# PSU_Board.net
KiCad netlist of a schematic drawn in EAGLE
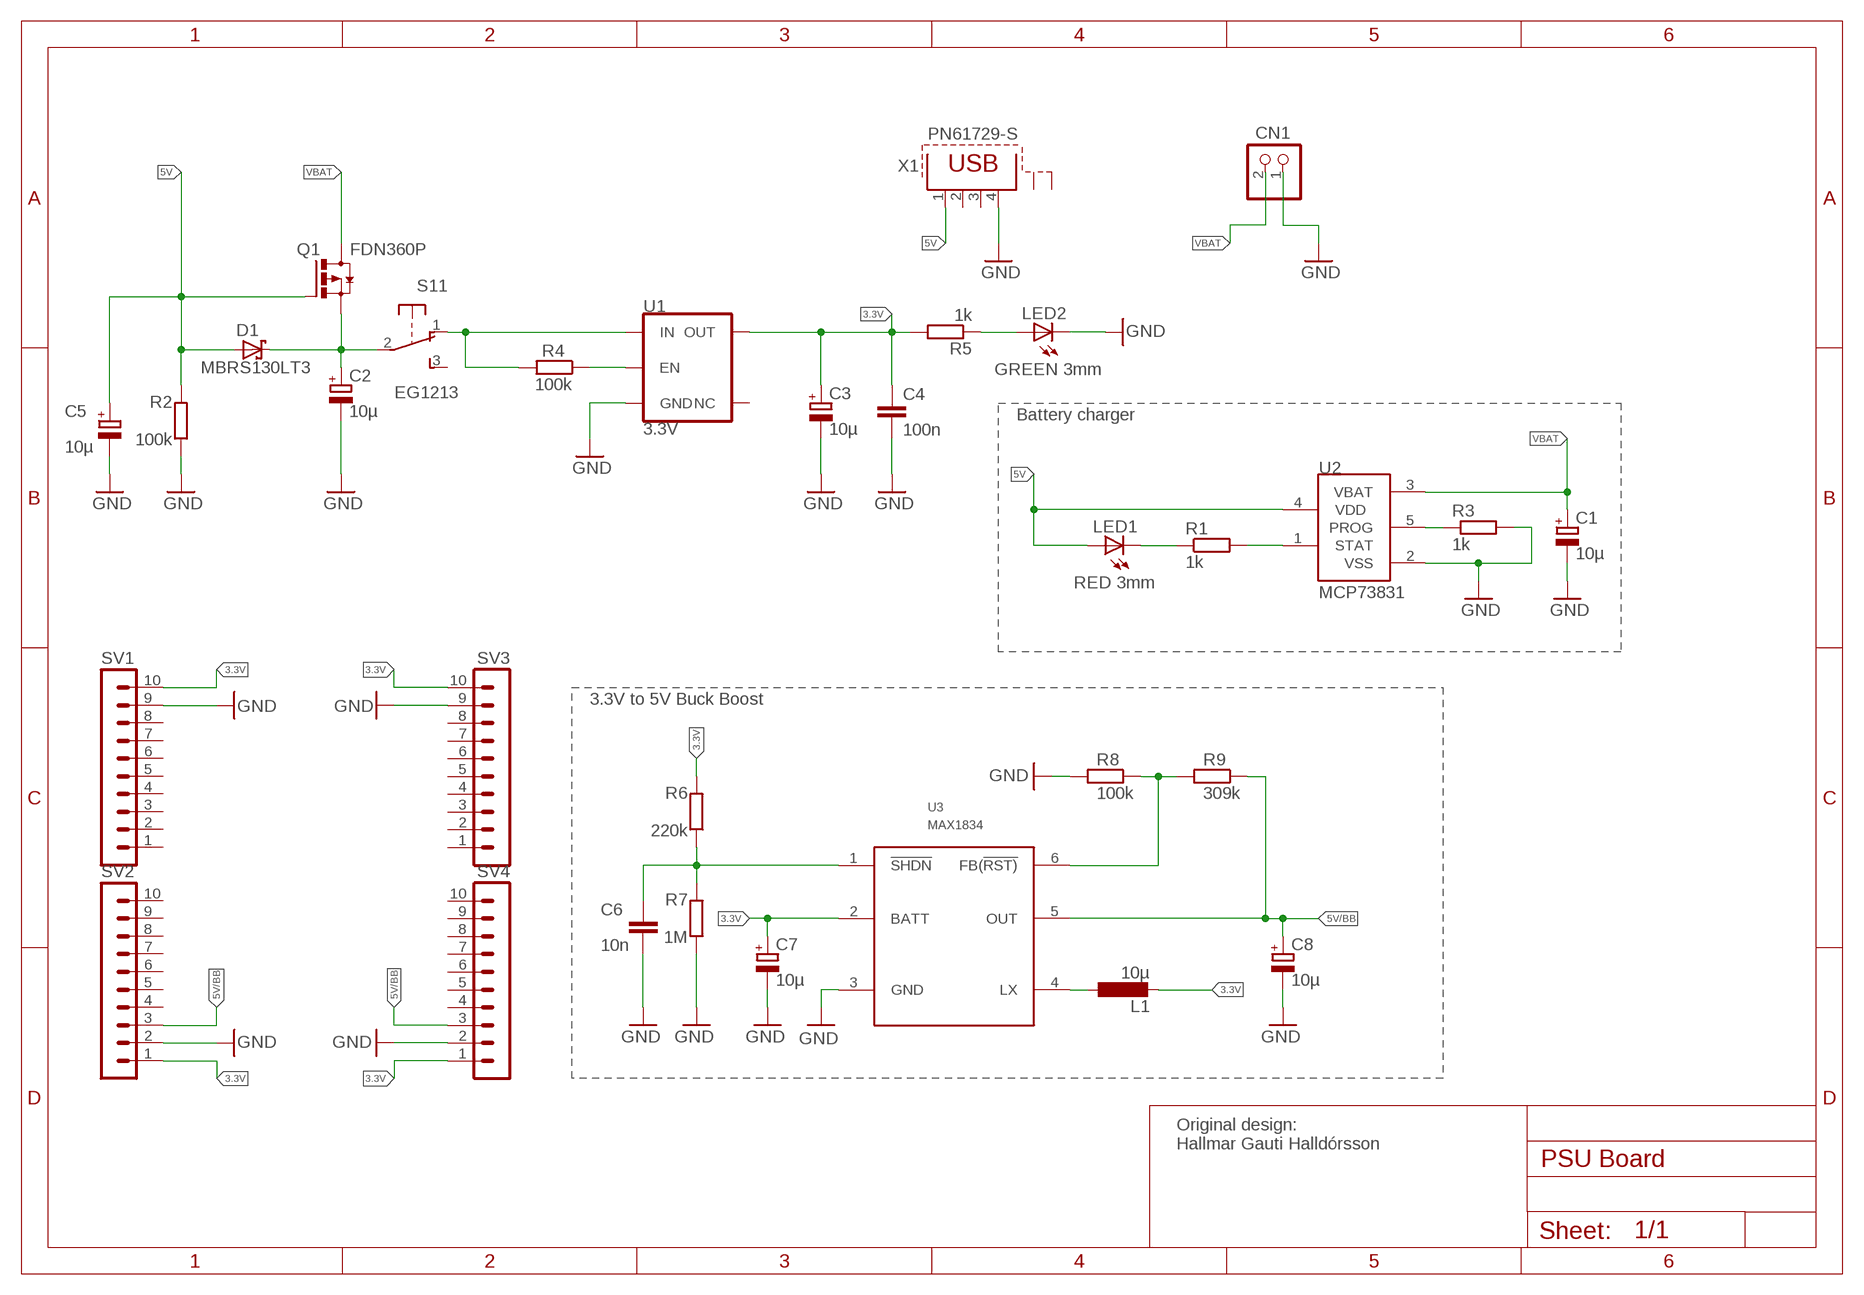
[diagram p0: schematic, sheet 1]

(export (version "E")
  (design (tool "Eeschema 10.0.6"))
  (components
    (comp (ref "C1")
      (value "10µ")
      (footprint "eagle-import:140CLH-0810")
      (libsource (lib "eagle-import") (part "CPOL-EU140CLH-0810"))
    )
    (comp (ref "C2")
      (value "10µ")
      (footprint "eagle-import:140CLH-0810")
      (libsource (lib "eagle-import") (part "CPOL-EU140CLH-0810"))
    )
    (comp (ref "C3")
      (value "10µ")
      (footprint "eagle-import:140CLH-0810")
      (libsource (lib "eagle-import") (part "CPOL-EU140CLH-0810"))
    )
    (comp (ref "C4")
      (value "100n")
      (footprint "eagle-import:C1206")
      (libsource (lib "eagle-import") (part "C-EUC1206"))
    )
    (comp (ref "C5")
      (value "10µ")
      (footprint "eagle-import:140CLH-0810")
      (libsource (lib "eagle-import") (part "CPOL-EU140CLH-0810"))
    )
    (comp (ref "C6")
      (value "10n")
      (footprint "eagle-import:C1206")
      (libsource (lib "eagle-import") (part "C-EUC1206"))
    )
    (comp (ref "C7")
      (value "10µ")
      (footprint "eagle-import:140CLH-0810")
      (libsource (lib "eagle-import") (part "CPOL-EU140CLH-0810"))
    )
    (comp (ref "C8")
      (value "10µ")
      (footprint "eagle-import:140CLH-0810")
      (libsource (lib "eagle-import") (part "CPOL-EU140CLH-0810"))
    )
    (comp (ref "CN1")
      (value "JST_2PIN-SMT")
      (footprint "eagle-import:JST-PH-2-SMT")
      (libsource (lib "eagle-import") (part "JST_2PIN-SMT"))
    )
    (comp (ref "D1")
      (value "MBRS130LT3")
      (footprint "eagle-import:SMB")
      (libsource (lib "eagle-import") (part "MBRS130LT3"))
    )
    (comp (ref "L1")
      (value "10µ")
      (footprint "eagle-import:L3216C")
      (libsource (lib "eagle-import") (part "L-EUL3216C"))
    )
    (comp (ref "LED1")
      (value "RED 3mm")
      (footprint "eagle-import:LED3MM")
      (libsource (lib "eagle-import") (part "LED3MM"))
    )
    (comp (ref "LED2")
      (value "GREEN 3mm")
      (footprint "eagle-import:LED3MM")
      (libsource (lib "eagle-import") (part "LED3MM"))
    )
    (comp (ref "Q1")
      (value "FDN360P")
      (footprint "eagle-import:SUPER-SOT3")
      (libsource (lib "eagle-import") (part "FDN360P"))
    )
    (comp (ref "R1")
      (value "1k")
      (footprint "eagle-import:M1206")
      (libsource (lib "eagle-import") (part "R-EU_M1206"))
    )
    (comp (ref "R2")
      (value "100k")
      (footprint "eagle-import:M1206")
      (libsource (lib "eagle-import") (part "R-EU_M1206"))
    )
    (comp (ref "R3")
      (value "1k")
      (footprint "eagle-import:M1206")
      (libsource (lib "eagle-import") (part "R-EU_M1206"))
    )
    (comp (ref "R4")
      (value "100k")
      (footprint "eagle-import:M1206")
      (libsource (lib "eagle-import") (part "R-EU_M1206"))
    )
    (comp (ref "R5")
      (value "1k")
      (footprint "eagle-import:M1206")
      (libsource (lib "eagle-import") (part "R-EU_M1206"))
    )
    (comp (ref "R6")
      (value "220k")
      (footprint "eagle-import:M1206")
      (libsource (lib "eagle-import") (part "R-EU_M1206"))
    )
    (comp (ref "R7")
      (value "1M")
      (footprint "eagle-import:M1206")
      (libsource (lib "eagle-import") (part "R-EU_M1206"))
    )
    (comp (ref "R8")
      (value "100k")
      (footprint "eagle-import:M1206")
      (libsource (lib "eagle-import") (part "R-EU_M1206"))
    )
    (comp (ref "R9")
      (value "309k")
      (footprint "eagle-import:M1206")
      (libsource (lib "eagle-import") (part "R-EU_M1206"))
    )
    (comp (ref "S1")
      (value "EG1213")
      (footprint "eagle-import:EG1213")
      (libsource (lib "eagle-import") (part "EG1213"))
    )
    (comp (ref "SV1")
      (value "MA10-1")
      (footprint "eagle-import:MA10-1")
      (libsource (lib "eagle-import") (part "MA10-1"))
    )
    (comp (ref "SV2")
      (value "MA10-1")
      (footprint "eagle-import:MA10-1")
      (libsource (lib "eagle-import") (part "MA10-1"))
    )
    (comp (ref "SV3")
      (value "MA10-1")
      (footprint "eagle-import:MA10-1")
      (libsource (lib "eagle-import") (part "MA10-1"))
    )
    (comp (ref "SV4")
      (value "MA10-1")
      (footprint "eagle-import:MA10-1")
      (libsource (lib "eagle-import") (part "MA10-1"))
    )
    (comp (ref "U1")
      (value "3.3V")
      (footprint "eagle-import:SOT23-5")
      (libsource (lib "eagle-import") (part "V_REG_AP2112K-3.3V"))
    )
    (comp (ref "U2")
      (value "MCP73831")
      (footprint "eagle-import:SOT23-5L")
      (libsource (lib "eagle-import") (part "MCP73831"))
    )
    (comp (ref "U3")
      (value "MAX1834")
      (footprint "eagle-import:SOT23-6")
      (libsource (lib "eagle-import") (part "MAX1834"))
    )
    (comp (ref "X1")
      (value "PN61729-S")
      (footprint "eagle-import:PN61729-S")
      (libsource (lib "eagle-import") (part "PN61729-S"))
    )
  )
  (nets
    (net (code "1") (name "3.3V") (class "Default")
      (node (ref "C3") (pin "+") (pinfunction "+_+") (pintype "passive"))
      (node (ref "C4") (pin "1") (pinfunction "1_1") (pintype "passive"))
      (node (ref "C7") (pin "+") (pinfunction "+_+") (pintype "passive"))
      (node (ref "L1") (pin "2") (pinfunction "2_2") (pintype "passive"))
      (node (ref "R5") (pin "2") (pinfunction "2_2") (pintype "passive"))
      (node (ref "R6") (pin "2") (pinfunction "2_2") (pintype "passive"))
      (node (ref "SV1") (pin "10") (pinfunction "10_10") (pintype "passive"))
      (node (ref "SV2") (pin "1") (pinfunction "1_1") (pintype "passive"))
      (node (ref "SV3") (pin "10") (pinfunction "10_10") (pintype "passive"))
      (node (ref "SV4") (pin "1") (pinfunction "1_1") (pintype "passive"))
      (node (ref "U1") (pin "5") (pinfunction "OUT_5") (pintype "passive"))
      (node (ref "U3") (pin "2") (pinfunction "BATT_2") (pintype "bidirectional"))
    )
    (net (code "2") (name "5V") (class "Default")
      (node (ref "C5") (pin "+") (pinfunction "+_+") (pintype "passive"))
      (node (ref "D1") (pin "A") (pinfunction "A_A") (pintype "passive"))
      (node (ref "LED1") (pin "A") (pinfunction "A_A") (pintype "passive"))
      (node (ref "Q1") (pin "1") (pinfunction "G_1") (pintype "passive"))
      (node (ref "R2") (pin "2") (pinfunction "2_2") (pintype "passive"))
      (node (ref "U2") (pin "4") (pinfunction "VDD_4") (pintype "bidirectional"))
      (node (ref "X1") (pin "1") (pinfunction "1_1") (pintype "passive"))
    )
    (net (code "3") (name "5V{slash}BB") (class "Default")
      (node (ref "C8") (pin "+") (pinfunction "+_+") (pintype "passive"))
      (node (ref "R9") (pin "1") (pinfunction "1_1") (pintype "passive"))
      (node (ref "SV2") (pin "3") (pinfunction "3_3") (pintype "passive"))
      (node (ref "SV4") (pin "3") (pinfunction "3_3") (pintype "passive"))
      (node (ref "U3") (pin "5") (pinfunction "OUT_5") (pintype "bidirectional"))
    )
    (net (code "4") (name "GND") (class "Default")
      (node (ref "C1") (pin "-") (pinfunction "-_-") (pintype "passive"))
      (node (ref "C2") (pin "-") (pinfunction "-_-") (pintype "passive"))
      (node (ref "C3") (pin "-") (pinfunction "-_-") (pintype "passive"))
      (node (ref "C4") (pin "2") (pinfunction "2_2") (pintype "passive"))
      (node (ref "C5") (pin "-") (pinfunction "-_-") (pintype "passive"))
      (node (ref "C6") (pin "2") (pinfunction "2_2") (pintype "passive"))
      (node (ref "C7") (pin "-") (pinfunction "-_-") (pintype "passive"))
      (node (ref "C8") (pin "-") (pinfunction "-_-") (pintype "passive"))
      (node (ref "CN1") (pin "1") (pinfunction "2_1") (pintype "passive"))
      (node (ref "LED2") (pin "K") (pinfunction "C_K") (pintype "passive"))
      (node (ref "R2") (pin "1") (pinfunction "1_1") (pintype "passive"))
      (node (ref "R3") (pin "2") (pinfunction "2_2") (pintype "passive"))
      (node (ref "R7") (pin "1") (pinfunction "1_1") (pintype "passive"))
      (node (ref "R8") (pin "2") (pinfunction "2_2") (pintype "passive"))
      (node (ref "SV1") (pin "9") (pinfunction "9_9") (pintype "passive"))
      (node (ref "SV2") (pin "2") (pinfunction "2_2") (pintype "passive"))
      (node (ref "SV3") (pin "9") (pinfunction "9_9") (pintype "passive"))
      (node (ref "SV4") (pin "2") (pinfunction "2_2") (pintype "passive"))
      (node (ref "U1") (pin "2") (pinfunction "GND_2") (pintype "input"))
      (node (ref "U2") (pin "2") (pinfunction "VSS_2") (pintype "bidirectional"))
      (node (ref "U3") (pin "3") (pinfunction "GND_3") (pintype "bidirectional"))
      (node (ref "X1") (pin "4") (pinfunction "4_4") (pintype "passive"))
    )
    (net (code "5") (name "Net-(LED1-C)") (class "Default")
      (node (ref "LED1") (pin "K") (pinfunction "C_K") (pintype "passive"))
      (node (ref "R1") (pin "1") (pinfunction "1_1") (pintype "passive"))
    )
    (net (code "6") (name "Net-(LED2-PadA)") (class "Default")
      (node (ref "LED2") (pin "A") (pinfunction "A_A") (pintype "passive"))
      (node (ref "R5") (pin "1") (pinfunction "1_1") (pintype "passive"))
    )
    (net (code "7") (name "Net-(Q1-S)") (class "Default")
      (node (ref "C2") (pin "+") (pinfunction "+_+") (pintype "passive"))
      (node (ref "D1") (pin "C") (pinfunction "C_C") (pintype "passive"))
      (node (ref "Q1") (pin "2") (pinfunction "S_2") (pintype "passive"))
      (node (ref "S1") (pin "2") (pinfunction "P_2") (pintype "passive"))
    )
    (net (code "8") (name "Net-(S1A-O)") (class "Default")
      (node (ref "R4") (pin "2") (pinfunction "2_2") (pintype "passive"))
      (node (ref "S1") (pin "1") (pinfunction "O_1") (pintype "passive"))
      (node (ref "U1") (pin "1") (pinfunction "IN_1") (pintype "input"))
    )
    (net (code "9") (name "Net-(U1-EN)") (class "Default")
      (node (ref "R4") (pin "1") (pinfunction "1_1") (pintype "passive"))
      (node (ref "U1") (pin "3") (pinfunction "EN_3") (pintype "input"))
    )
    (net (code "10") (name "Net-(U2-PROG)") (class "Default")
      (node (ref "R3") (pin "1") (pinfunction "1_1") (pintype "passive"))
      (node (ref "U2") (pin "5") (pinfunction "PROG_5") (pintype "bidirectional"))
    )
    (net (code "11") (name "Net-(U2-STAT)") (class "Default")
      (node (ref "R1") (pin "2") (pinfunction "2_2") (pintype "passive"))
      (node (ref "U2") (pin "1") (pinfunction "STAT_1") (pintype "bidirectional"))
    )
    (net (code "12") (name "Net-(U3-FB(~{RST}))") (class "Default")
      (node (ref "R8") (pin "1") (pinfunction "1_1") (pintype "passive"))
      (node (ref "R9") (pin "2") (pinfunction "2_2") (pintype "passive"))
      (node (ref "U3") (pin "6") (pinfunction "FB(~{RST})_6") (pintype "bidirectional"))
    )
    (net (code "13") (name "Net-(U3-LX)") (class "Default")
      (node (ref "L1") (pin "1") (pinfunction "1_1") (pintype "passive"))
      (node (ref "U3") (pin "4") (pinfunction "LX_4") (pintype "bidirectional"))
    )
    (net (code "14") (name "Net-(U3-~{SHDN})") (class "Default")
      (node (ref "C6") (pin "1") (pinfunction "1_1") (pintype "passive"))
      (node (ref "R6") (pin "1") (pinfunction "1_1") (pintype "passive"))
      (node (ref "R7") (pin "2") (pinfunction "2_2") (pintype "passive"))
      (node (ref "U3") (pin "1") (pinfunction "~{SHDN}_1") (pintype "bidirectional"))
    )
    (net (code "15") (name "VBAT") (class "Default")
      (node (ref "C1") (pin "+") (pinfunction "+_+") (pintype "passive"))
      (node (ref "CN1") (pin "2") (pinfunction "1_2") (pintype "passive"))
      (node (ref "Q1") (pin "3") (pinfunction "D_3") (pintype "passive"))
      (node (ref "U2") (pin "3") (pinfunction "VBAT_3") (pintype "bidirectional"))
    )
    (net (code "16") (name "unconnected-(S1A-S-Pad3)") (class "Default")
      (node (ref "S1") (pin "3") (pinfunction "S_3") (pintype "passive"))
    )
    (net (code "17") (name "unconnected-(SV1-Pad1)") (class "Default")
      (node (ref "SV1") (pin "1") (pinfunction "1_1") (pintype "passive"))
    )
    (net (code "18") (name "unconnected-(SV1-Pad2)") (class "Default")
      (node (ref "SV1") (pin "2") (pinfunction "2_2") (pintype "passive"))
    )
    (net (code "19") (name "unconnected-(SV1-Pad3)") (class "Default")
      (node (ref "SV1") (pin "3") (pinfunction "3_3") (pintype "passive"))
    )
    (net (code "20") (name "unconnected-(SV1-Pad4)") (class "Default")
      (node (ref "SV1") (pin "4") (pinfunction "4_4") (pintype "passive"))
    )
    (net (code "21") (name "unconnected-(SV1-Pad5)") (class "Default")
      (node (ref "SV1") (pin "5") (pinfunction "5_5") (pintype "passive"))
    )
    (net (code "22") (name "unconnected-(SV1-Pad6)") (class "Default")
      (node (ref "SV1") (pin "6") (pinfunction "6_6") (pintype "passive"))
    )
    (net (code "23") (name "unconnected-(SV1-Pad7)") (class "Default")
      (node (ref "SV1") (pin "7") (pinfunction "7_7") (pintype "passive"))
    )
    (net (code "24") (name "unconnected-(SV1-Pad8)") (class "Default")
      (node (ref "SV1") (pin "8") (pinfunction "8_8") (pintype "passive"))
    )
    (net (code "25") (name "unconnected-(SV2-Pad4)") (class "Default")
      (node (ref "SV2") (pin "4") (pinfunction "4_4") (pintype "passive"))
    )
    (net (code "26") (name "unconnected-(SV2-Pad5)") (class "Default")
      (node (ref "SV2") (pin "5") (pinfunction "5_5") (pintype "passive"))
    )
    (net (code "27") (name "unconnected-(SV2-Pad6)") (class "Default")
      (node (ref "SV2") (pin "6") (pinfunction "6_6") (pintype "passive"))
    )
    (net (code "28") (name "unconnected-(SV2-Pad7)") (class "Default")
      (node (ref "SV2") (pin "7") (pinfunction "7_7") (pintype "passive"))
    )
    (net (code "29") (name "unconnected-(SV2-Pad8)") (class "Default")
      (node (ref "SV2") (pin "8") (pinfunction "8_8") (pintype "passive"))
    )
    (net (code "30") (name "unconnected-(SV2-Pad9)") (class "Default")
      (node (ref "SV2") (pin "9") (pinfunction "9_9") (pintype "passive"))
    )
    (net (code "31") (name "unconnected-(SV2-Pad10)") (class "Default")
      (node (ref "SV2") (pin "10") (pinfunction "10_10") (pintype "passive"))
    )
    (net (code "32") (name "unconnected-(SV3-Pad1)") (class "Default")
      (node (ref "SV3") (pin "1") (pinfunction "1_1") (pintype "passive"))
    )
    (net (code "33") (name "unconnected-(SV3-Pad2)") (class "Default")
      (node (ref "SV3") (pin "2") (pinfunction "2_2") (pintype "passive"))
    )
    (net (code "34") (name "unconnected-(SV3-Pad3)") (class "Default")
      (node (ref "SV3") (pin "3") (pinfunction "3_3") (pintype "passive"))
    )
    (net (code "35") (name "unconnected-(SV3-Pad4)") (class "Default")
      (node (ref "SV3") (pin "4") (pinfunction "4_4") (pintype "passive"))
    )
    (net (code "36") (name "unconnected-(SV3-Pad5)") (class "Default")
      (node (ref "SV3") (pin "5") (pinfunction "5_5") (pintype "passive"))
    )
    (net (code "37") (name "unconnected-(SV3-Pad6)") (class "Default")
      (node (ref "SV3") (pin "6") (pinfunction "6_6") (pintype "passive"))
    )
    (net (code "38") (name "unconnected-(SV3-Pad7)") (class "Default")
      (node (ref "SV3") (pin "7") (pinfunction "7_7") (pintype "passive"))
    )
    (net (code "39") (name "unconnected-(SV3-Pad8)") (class "Default")
      (node (ref "SV3") (pin "8") (pinfunction "8_8") (pintype "passive"))
    )
    (net (code "40") (name "unconnected-(SV4-Pad4)") (class "Default")
      (node (ref "SV4") (pin "4") (pinfunction "4_4") (pintype "passive"))
    )
    (net (code "41") (name "unconnected-(SV4-Pad5)") (class "Default")
      (node (ref "SV4") (pin "5") (pinfunction "5_5") (pintype "passive"))
    )
    (net (code "42") (name "unconnected-(SV4-Pad6)") (class "Default")
      (node (ref "SV4") (pin "6") (pinfunction "6_6") (pintype "passive"))
    )
    (net (code "43") (name "unconnected-(SV4-Pad7)") (class "Default")
      (node (ref "SV4") (pin "7") (pinfunction "7_7") (pintype "passive"))
    )
    (net (code "44") (name "unconnected-(SV4-Pad8)") (class "Default")
      (node (ref "SV4") (pin "8") (pinfunction "8_8") (pintype "passive"))
    )
    (net (code "45") (name "unconnected-(SV4-Pad9)") (class "Default")
      (node (ref "SV4") (pin "9") (pinfunction "9_9") (pintype "passive"))
    )
    (net (code "46") (name "unconnected-(SV4-Pad10)") (class "Default")
      (node (ref "SV4") (pin "10") (pinfunction "10_10") (pintype "passive"))
    )
    (net (code "47") (name "unconnected-(U1-NC-Pad4)") (class "Default")
      (node (ref "U1") (pin "4") (pinfunction "NC_4") (pintype "no_connect"))
    )
    (net (code "48") (name "unconnected-(X1-Pad2)") (class "Default")
      (node (ref "X1") (pin "2") (pinfunction "2_2") (pintype "passive"))
    )
    (net (code "49") (name "unconnected-(X1-Pad3)") (class "Default")
      (node (ref "X1") (pin "3") (pinfunction "3_3") (pintype "passive"))
    )
    (net (code "50") (name "unconnected-(X1-PadS1)") (class "Default")
      (node (ref "X1") (pin "S1") (pinfunction "S1_S1") (pintype "passive"))
    )
    (net (code "51") (name "unconnected-(X1-PadS2)") (class "Default")
      (node (ref "X1") (pin "S2") (pinfunction "S2_S2") (pintype "passive"))
    )
  )
)
